# xmas_tree_pcb_B.net
KiCad netlist of a schematic drawn in EAGLE
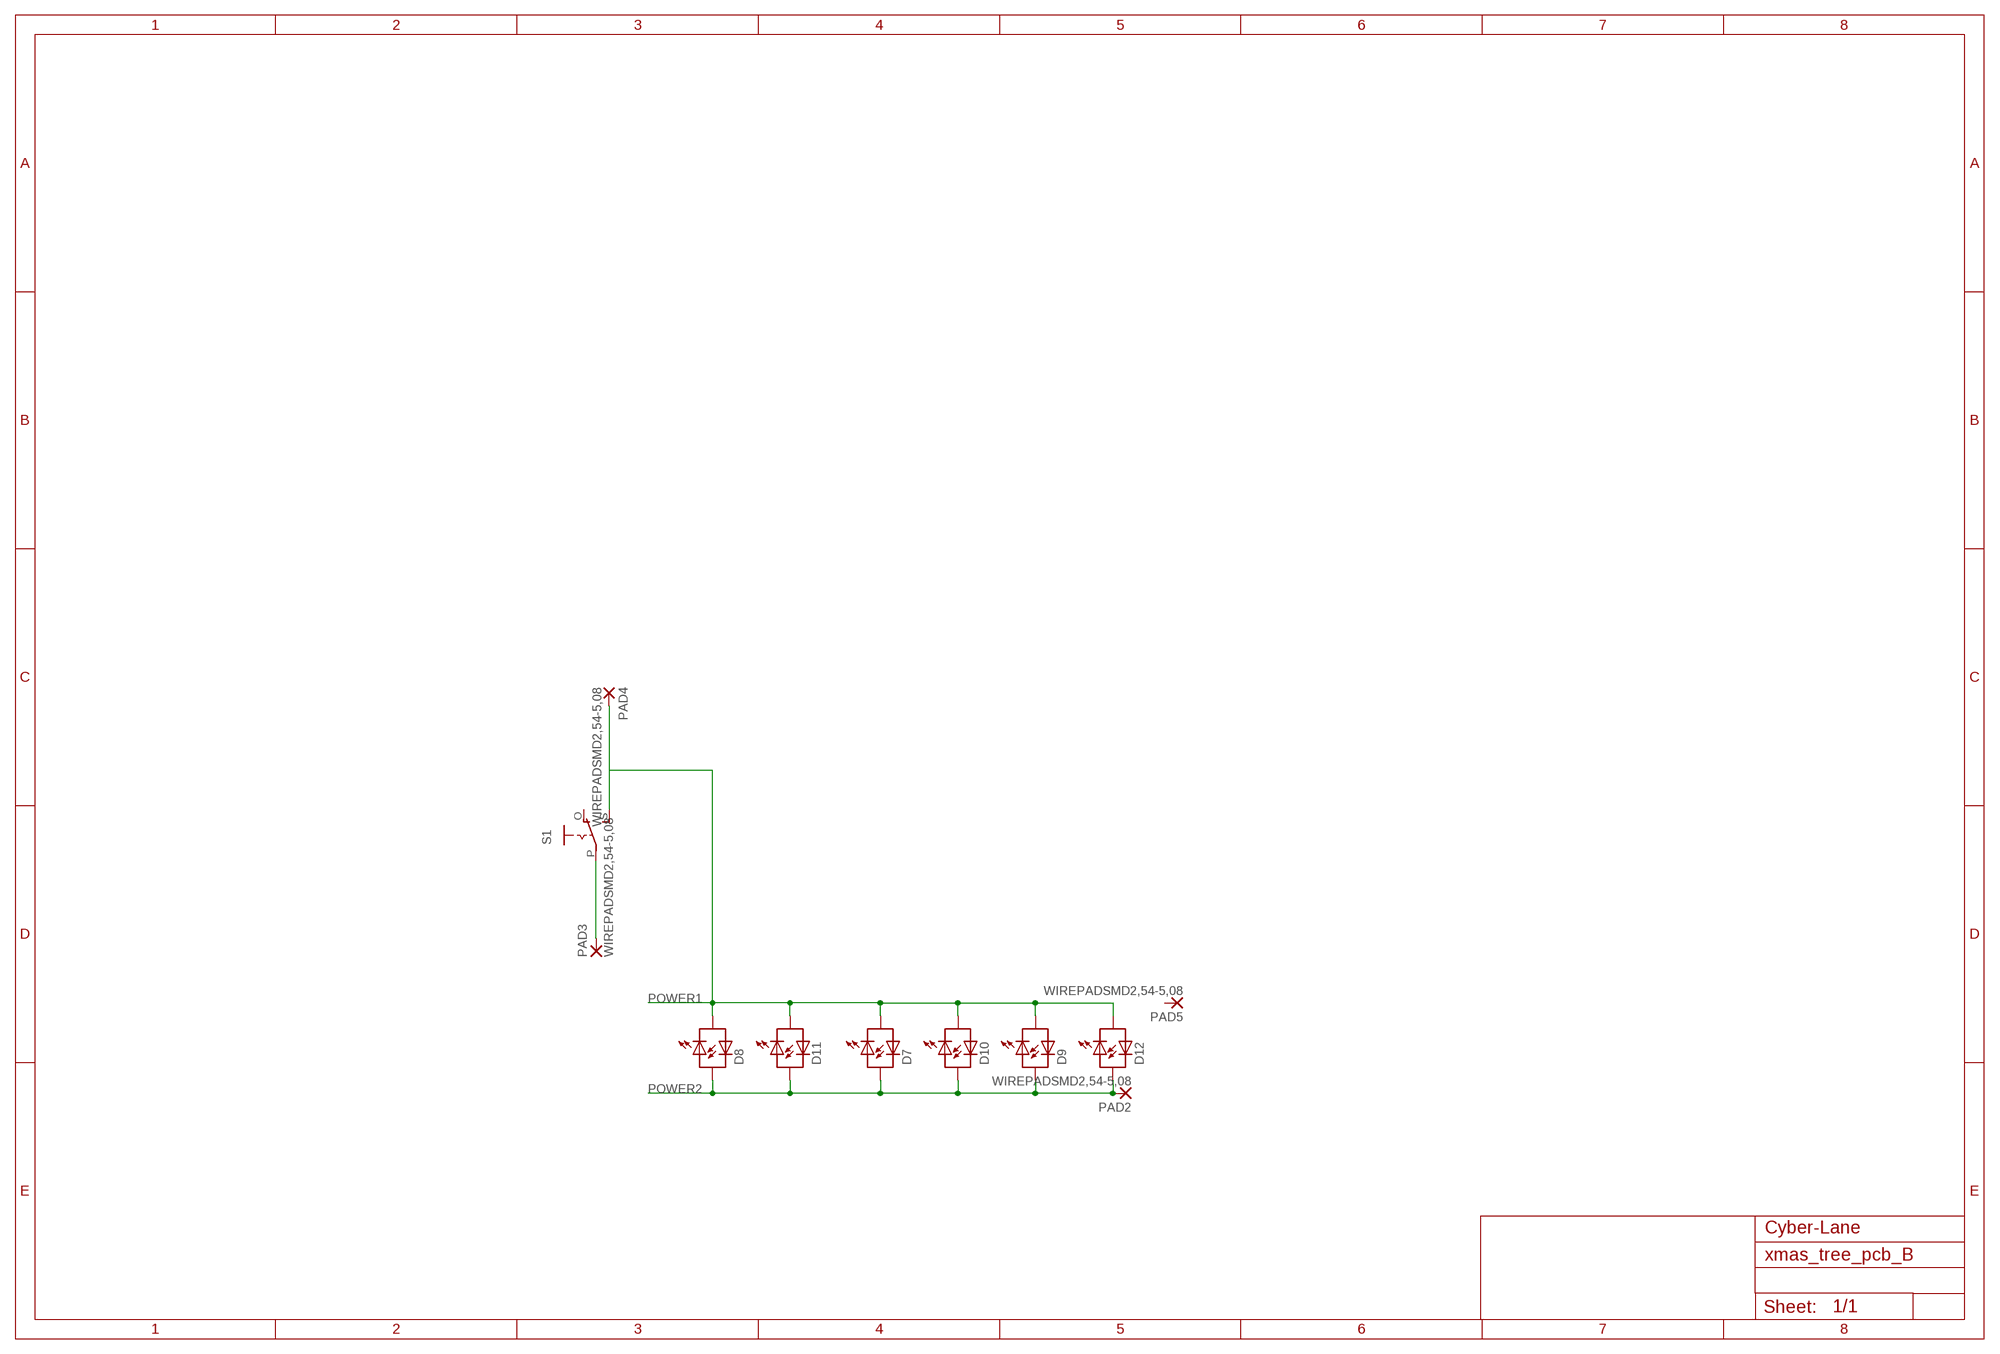
[diagram p0: schematic, sheet 1]

(export (version "E")
  (design (tool "Eeschema 10.0.6"))
  (components
    (comp (ref "D7")
      (value "LED_BI_COLOR")
      (footprint "eagle-import:LED3MM")
      (libsource (lib "eagle-import") (part "LED_BI_COLOR"))
    )
    (comp (ref "D8")
      (value "LED_BI_COLOR")
      (footprint "eagle-import:LED3MM")
      (libsource (lib "eagle-import") (part "LED_BI_COLOR"))
    )
    (comp (ref "D9")
      (value "LED_BI_COLOR")
      (footprint "eagle-import:LED3MM")
      (libsource (lib "eagle-import") (part "LED_BI_COLOR"))
    )
    (comp (ref "D10")
      (value "LED_BI_COLOR")
      (footprint "eagle-import:LED3MM")
      (libsource (lib "eagle-import") (part "LED_BI_COLOR"))
    )
    (comp (ref "D11")
      (value "LED_BI_COLOR")
      (footprint "eagle-import:LED3MM")
      (libsource (lib "eagle-import") (part "LED_BI_COLOR"))
    )
    (comp (ref "D12")
      (value "LED_BI_COLOR")
      (footprint "eagle-import:LED3MM")
      (libsource (lib "eagle-import") (part "LED_BI_COLOR"))
    )
    (comp (ref "PAD2")
      (value "WIREPADSMD2,54-5,08")
      (footprint "eagle-import:SMD2,54-5,08")
      (libsource (lib "eagle-import") (part "WIREPADSMD2,54-5,08"))
    )
    (comp (ref "PAD3")
      (value "WIREPADSMD2,54-5,08")
      (footprint "eagle-import:SMD2,54-5,08")
      (libsource (lib "eagle-import") (part "WIREPADSMD2,54-5,08"))
    )
    (comp (ref "PAD4")
      (value "WIREPADSMD2,54-5,08")
      (footprint "eagle-import:SMD2,54-5,08")
      (libsource (lib "eagle-import") (part "WIREPADSMD2,54-5,08"))
    )
    (comp (ref "PAD5")
      (value "WIREPADSMD2,54-5,08")
      (footprint "eagle-import:SMD2,54-5,08")
      (libsource (lib "eagle-import") (part "WIREPADSMD2,54-5,08"))
    )
    (comp (ref "S1")
      (value "EG1218S")
      (footprint "eagle-import:EG1218")
      (libsource (lib "eagle-import") (part "EG1218S"))
    )
  )
  (nets
    (net (code "1") (name "/POWER1") (class "Default")
      (node (ref "D10") (pin "K") (pinfunction "C1_K") (pintype "passive"))
      (node (ref "D11") (pin "K") (pinfunction "C1_K") (pintype "passive"))
      (node (ref "D12") (pin "K") (pinfunction "C1_K") (pintype "passive"))
      (node (ref "D7") (pin "K") (pinfunction "C1_K") (pintype "passive"))
      (node (ref "D8") (pin "K") (pinfunction "C1_K") (pintype "passive"))
      (node (ref "D9") (pin "K") (pinfunction "C1_K") (pintype "passive"))
      (node (ref "PAD4") (pin "1") (pinfunction "P_1") (pintype "passive"))
      (node (ref "S1") (pin "S") (pinfunction "S_S") (pintype "passive"))
    )
    (net (code "2") (name "/POWER2") (class "Default")
      (node (ref "D10") (pin "A") (pinfunction "A1_A") (pintype "passive"))
      (node (ref "D11") (pin "A") (pinfunction "A1_A") (pintype "passive"))
      (node (ref "D12") (pin "A") (pinfunction "A1_A") (pintype "passive"))
      (node (ref "D7") (pin "A") (pinfunction "A1_A") (pintype "passive"))
      (node (ref "D8") (pin "A") (pinfunction "A1_A") (pintype "passive"))
      (node (ref "D9") (pin "A") (pinfunction "A1_A") (pintype "passive"))
      (node (ref "PAD2") (pin "1") (pinfunction "P_1") (pintype "passive"))
    )
    (net (code "3") (name "Net-(PAD3-P)") (class "Default")
      (node (ref "PAD3") (pin "1") (pinfunction "P_1") (pintype "passive"))
      (node (ref "S1") (pin "P") (pinfunction "P_P") (pintype "passive"))
    )
    (net (code "4") (name "unconnected-(PAD5-P-Pad1)") (class "Default")
      (node (ref "PAD5") (pin "1") (pinfunction "P_1") (pintype "passive"))
    )
    (net (code "5") (name "unconnected-(S1-PadO)") (class "Default")
      (node (ref "S1") (pin "O") (pinfunction "O_O") (pintype "passive"))
    )
  )
)
